# tripoint.net
KiCad netlist of a schematic drawn in EAGLE
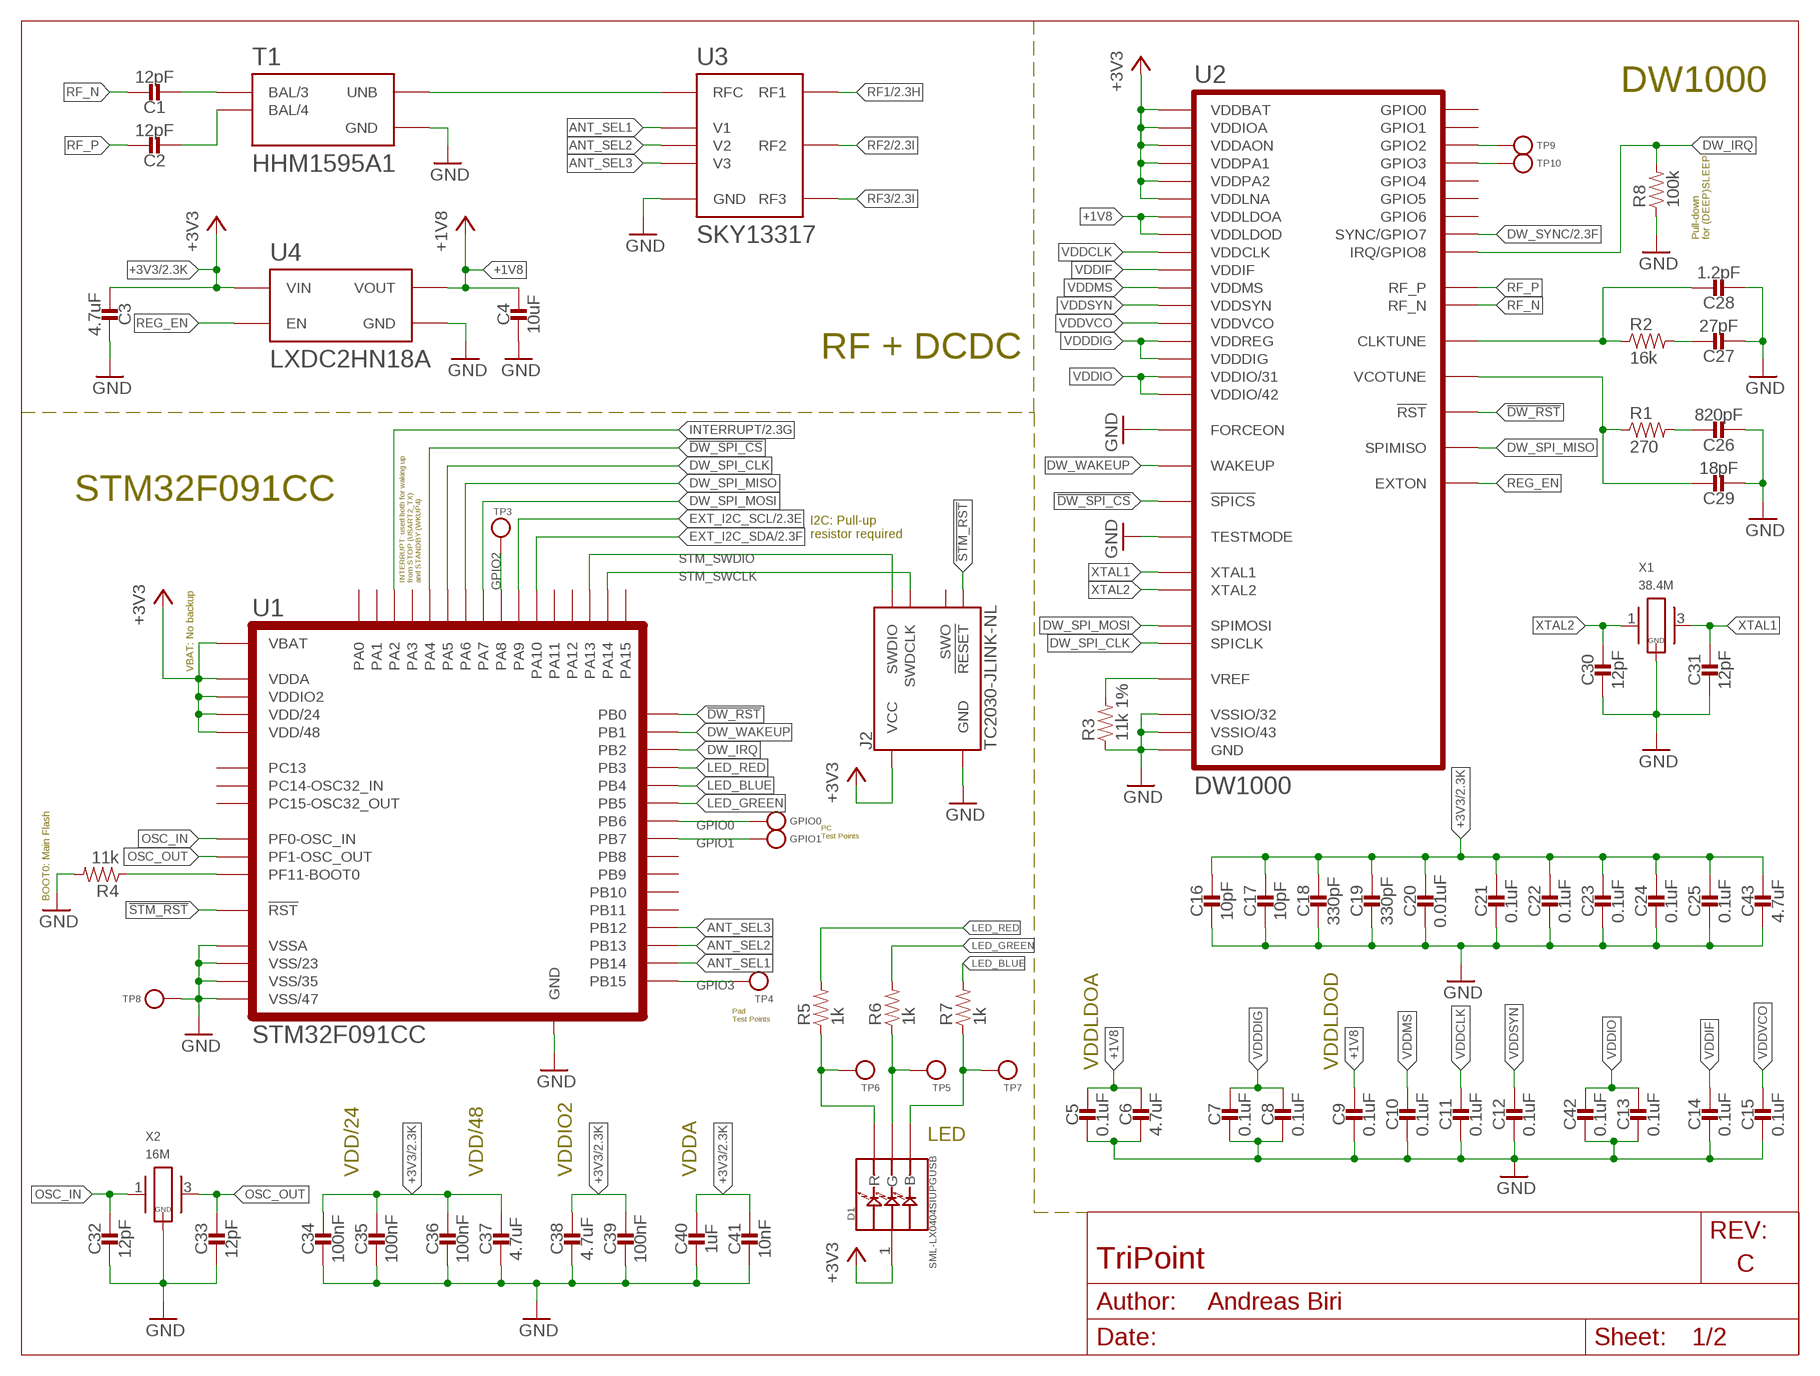
[diagram p0: schematic, sheet 1]
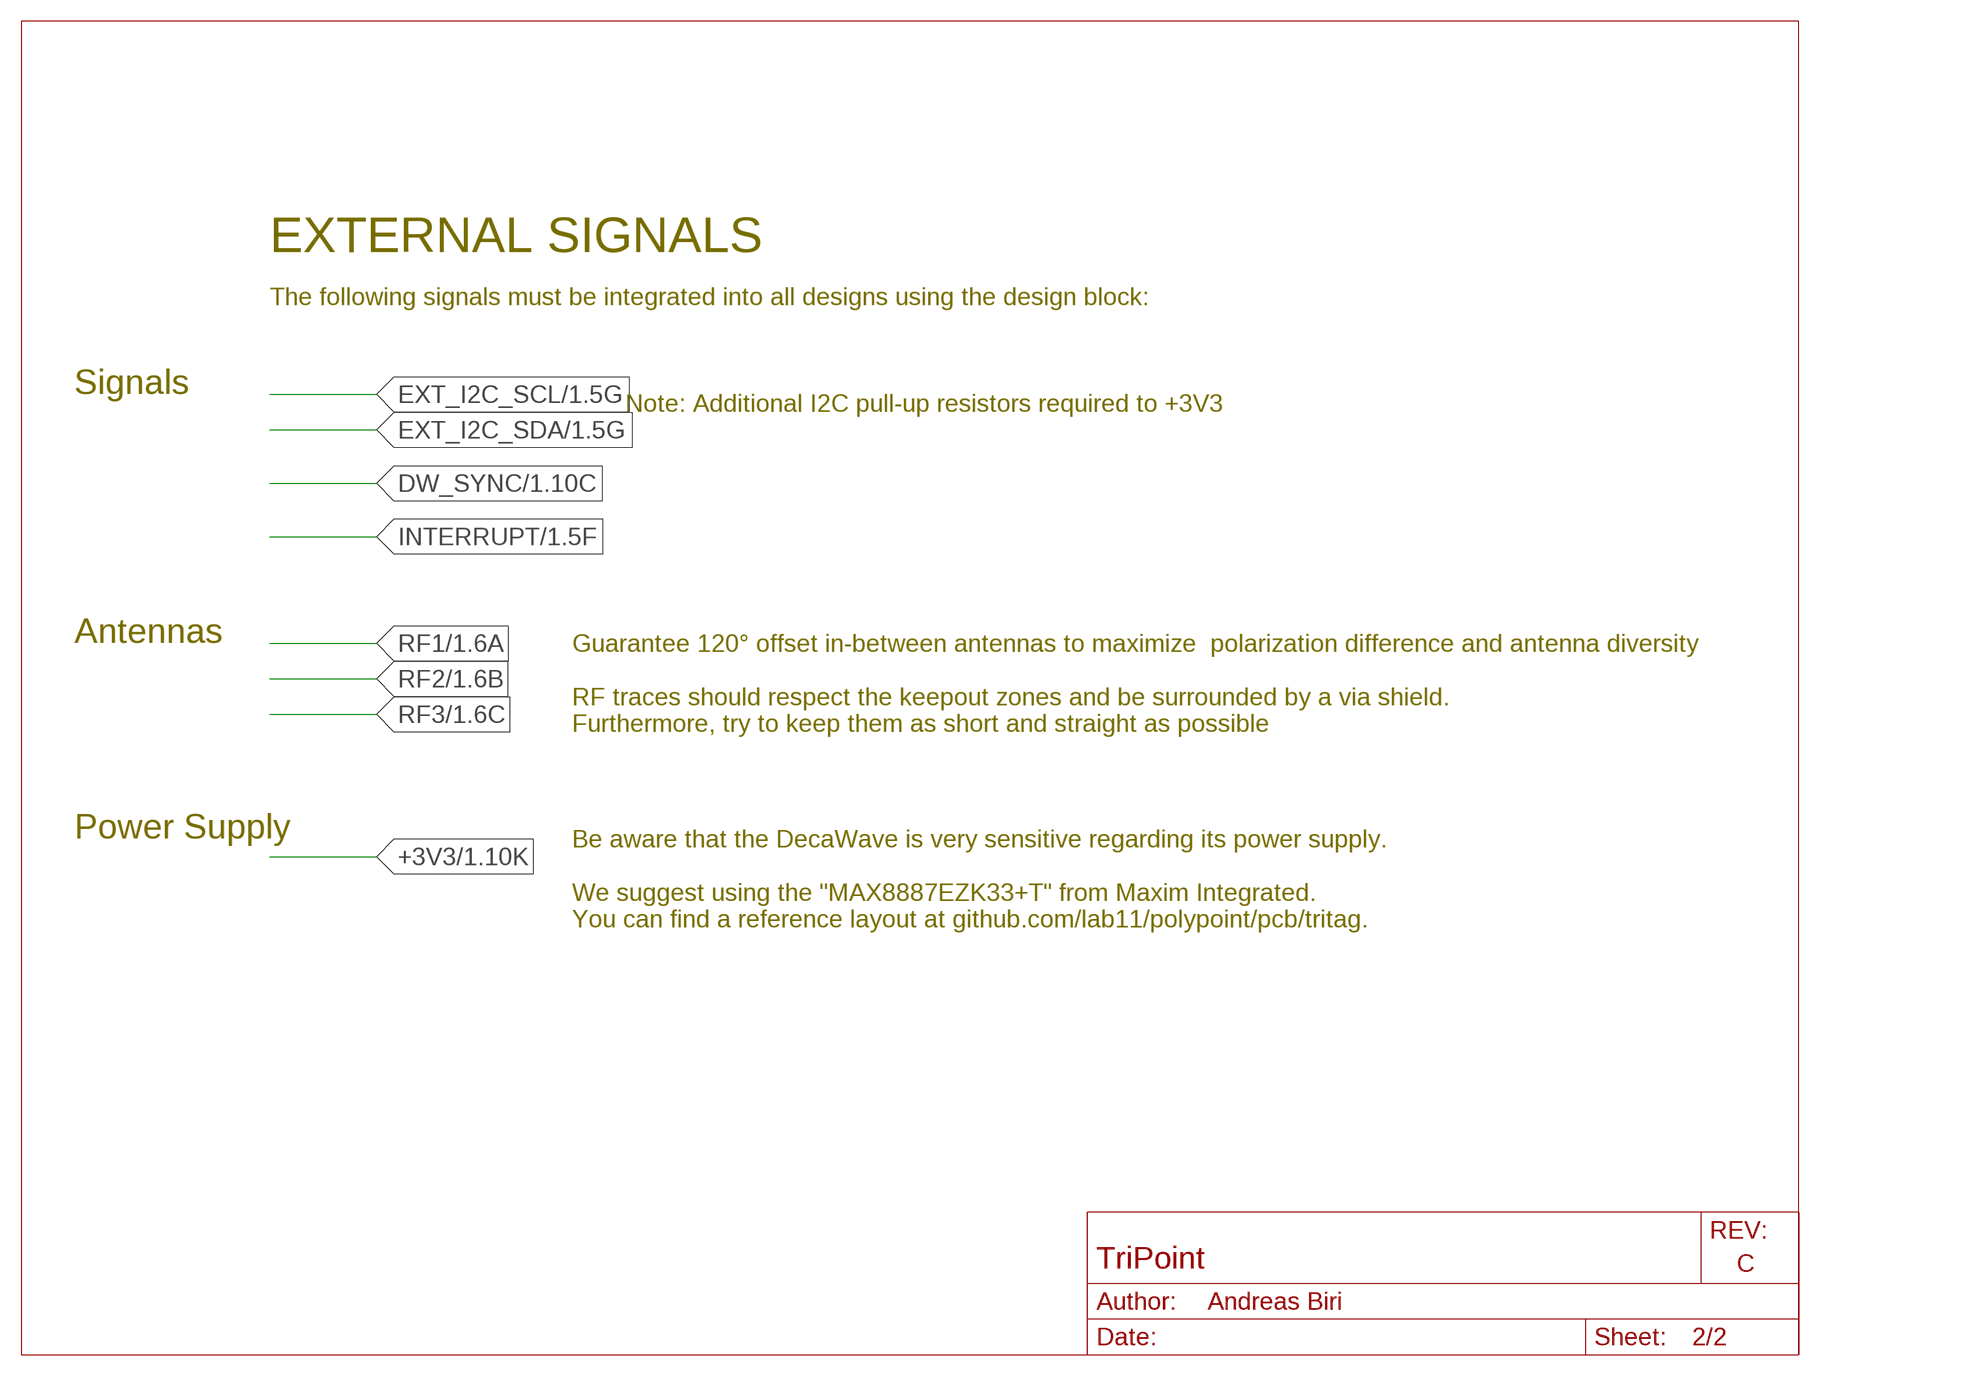
[diagram p1: schematic, sheet 2]

(export (version "E")
  (design (tool "Eeschema 10.0.6"))
  (components
    (comp (ref "C1")
      (value "12pF")
      (footprint "eagle-import:0201_CAP")
      (libsource (lib "eagle-import") (part "CAPACITOR0201_CAP"))
    )
    (comp (ref "C2")
      (value "12pF")
      (footprint "eagle-import:0201_CAP")
      (libsource (lib "eagle-import") (part "CAPACITOR0201_CAP"))
    )
    (comp (ref "C3")
      (value "4.7uF")
      (footprint "eagle-import:0402_CAP")
      (libsource (lib "eagle-import") (part "CAPACITOR0402_CAP"))
    )
    (comp (ref "C4")
      (value "10uF")
      (footprint "eagle-import:0603_CAP")
      (libsource (lib "eagle-import") (part "CAPACITOR0603_CAP"))
    )
    (comp (ref "C5")
      (value "0.1uF")
      (footprint "eagle-import:0402_CAP")
      (libsource (lib "eagle-import") (part "CAPACITOR0402_CAP"))
    )
    (comp (ref "C6")
      (value "4.7uF")
      (footprint "eagle-import:0402_CAP")
      (libsource (lib "eagle-import") (part "CAPACITOR0402_CAP"))
    )
    (comp (ref "C7")
      (value "0.1uF")
      (footprint "eagle-import:0402_CAP")
      (libsource (lib "eagle-import") (part "CAPACITOR0402_CAP"))
    )
    (comp (ref "C8")
      (value "0.1uF")
      (footprint "eagle-import:0402_CAP")
      (libsource (lib "eagle-import") (part "CAPACITOR0402_CAP"))
    )
    (comp (ref "C9")
      (value "0.1uF")
      (footprint "eagle-import:0402_CAP")
      (libsource (lib "eagle-import") (part "CAPACITOR0402_CAP"))
    )
    (comp (ref "C10")
      (value "0.1uF")
      (footprint "eagle-import:0402_CAP")
      (libsource (lib "eagle-import") (part "CAPACITOR0402_CAP"))
    )
    (comp (ref "C11")
      (value "0.1uF")
      (footprint "eagle-import:0402_CAP")
      (libsource (lib "eagle-import") (part "CAPACITOR0402_CAP"))
    )
    (comp (ref "C12")
      (value "0.1uF")
      (footprint "eagle-import:0402_CAP")
      (libsource (lib "eagle-import") (part "CAPACITOR0402_CAP"))
    )
    (comp (ref "C13")
      (value "0.1uF")
      (footprint "eagle-import:0402_CAP")
      (libsource (lib "eagle-import") (part "CAPACITOR0402_CAP"))
    )
    (comp (ref "C14")
      (value "0.1uF")
      (footprint "eagle-import:0402_CAP")
      (libsource (lib "eagle-import") (part "CAPACITOR0402_CAP"))
    )
    (comp (ref "C15")
      (value "0.1uF")
      (footprint "eagle-import:0402_CAP")
      (libsource (lib "eagle-import") (part "CAPACITOR0402_CAP"))
    )
    (comp (ref "C16")
      (value "10pF")
      (footprint "eagle-import:0402_CAP")
      (libsource (lib "eagle-import") (part "CAPACITOR0402_CAP"))
    )
    (comp (ref "C17")
      (value "10pF")
      (footprint "eagle-import:0402_CAP")
      (libsource (lib "eagle-import") (part "CAPACITOR0402_CAP"))
    )
    (comp (ref "C18")
      (value "330pF")
      (footprint "eagle-import:0402_CAP")
      (libsource (lib "eagle-import") (part "CAPACITOR0402_CAP"))
    )
    (comp (ref "C19")
      (value "330pF")
      (footprint "eagle-import:0402_CAP")
      (libsource (lib "eagle-import") (part "CAPACITOR0402_CAP"))
    )
    (comp (ref "C20")
      (value "0.01uF")
      (footprint "eagle-import:0402_CAP")
      (libsource (lib "eagle-import") (part "CAPACITOR0402_CAP"))
    )
    (comp (ref "C21")
      (value "0.1uF")
      (footprint "eagle-import:0402_CAP")
      (libsource (lib "eagle-import") (part "CAPACITOR0402_CAP"))
    )
    (comp (ref "C22")
      (value "0.1uF")
      (footprint "eagle-import:0402_CAP")
      (libsource (lib "eagle-import") (part "CAPACITOR0402_CAP"))
    )
    (comp (ref "C23")
      (value "0.1uF")
      (footprint "eagle-import:0402_CAP")
      (libsource (lib "eagle-import") (part "CAPACITOR0402_CAP"))
    )
    (comp (ref "C24")
      (value "0.1uF")
      (footprint "eagle-import:0402_CAP")
      (libsource (lib "eagle-import") (part "CAPACITOR0402_CAP"))
    )
    (comp (ref "C25")
      (value "0.1uF")
      (footprint "eagle-import:0402_CAP")
      (libsource (lib "eagle-import") (part "CAPACITOR0402_CAP"))
    )
    (comp (ref "C26")
      (value "820pF")
      (footprint "eagle-import:0402_CAP")
      (libsource (lib "eagle-import") (part "CAPACITOR0402_CAP"))
    )
    (comp (ref "C27")
      (value "27pF")
      (footprint "eagle-import:0402_CAP")
      (libsource (lib "eagle-import") (part "CAPACITOR0402_CAP"))
    )
    (comp (ref "C28")
      (value "1.2pF")
      (footprint "eagle-import:0402_CAP")
      (libsource (lib "eagle-import") (part "CAPACITOR0402_CAP"))
    )
    (comp (ref "C29")
      (value "18pF")
      (footprint "eagle-import:0402_CAP")
      (libsource (lib "eagle-import") (part "CAPACITOR0402_CAP"))
    )
    (comp (ref "C30")
      (value "12pF")
      (footprint "eagle-import:0402_CAP")
      (libsource (lib "eagle-import") (part "CAPACITOR0402_CAP"))
    )
    (comp (ref "C31")
      (value "12pF")
      (footprint "eagle-import:0402_CAP")
      (libsource (lib "eagle-import") (part "CAPACITOR0402_CAP"))
    )
    (comp (ref "C32")
      (value "12pF")
      (footprint "eagle-import:0402_CAP")
      (libsource (lib "eagle-import") (part "CAPACITOR0402_CAP"))
    )
    (comp (ref "C33")
      (value "12pF")
      (footprint "eagle-import:0402_CAP")
      (libsource (lib "eagle-import") (part "CAPACITOR0402_CAP"))
    )
    (comp (ref "C34")
      (value "100nF")
      (footprint "eagle-import:0402_CAP")
      (libsource (lib "eagle-import") (part "CAPACITOR0402_CAP"))
    )
    (comp (ref "C35")
      (value "100nF")
      (footprint "eagle-import:0402_CAP")
      (libsource (lib "eagle-import") (part "CAPACITOR0402_CAP"))
    )
    (comp (ref "C36")
      (value "100nF")
      (footprint "eagle-import:0402_CAP")
      (libsource (lib "eagle-import") (part "CAPACITOR0402_CAP"))
    )
    (comp (ref "C37")
      (value "4.7uF")
      (footprint "eagle-import:0402_CAP")
      (libsource (lib "eagle-import") (part "CAPACITOR0402_CAP"))
    )
    (comp (ref "C38")
      (value "4.7uF")
      (footprint "eagle-import:0402_CAP")
      (libsource (lib "eagle-import") (part "CAPACITOR0402_CAP"))
    )
    (comp (ref "C39")
      (value "100nF")
      (footprint "eagle-import:0402_CAP")
      (libsource (lib "eagle-import") (part "CAPACITOR0402_CAP"))
    )
    (comp (ref "C40")
      (value "1uF")
      (footprint "eagle-import:0402_CAP")
      (libsource (lib "eagle-import") (part "CAPACITOR0402_CAP"))
    )
    (comp (ref "C41")
      (value "10nF")
      (footprint "eagle-import:0402_CAP")
      (libsource (lib "eagle-import") (part "CAPACITOR0402_CAP"))
    )
    (comp (ref "C42")
      (value "0.1uF")
      (footprint "eagle-import:0402_CAP")
      (libsource (lib "eagle-import") (part "CAPACITOR0402_CAP"))
    )
    (comp (ref "C43")
      (value "4.7uF")
      (footprint "eagle-import:0402_CAP")
      (libsource (lib "eagle-import") (part "CAPACITOR0402_CAP"))
    )
    (comp (ref "D1")
      (value "SML-LX0404SIUPGUSB")
      (footprint "eagle-import:1MM_SQ_4PAD")
      (fields (field (name "MANUFACTURER") "Lumex Opto"))
      (libsource (lib "eagle-import") (part "SML-LX0404SIUPGUSB"))
    )
    (comp (ref "GPIO0")
      (value "TEST_POINT_0.040IN")
      (footprint "eagle-import:TESTPOINT_0.040IN")
      (libsource (lib "eagle-import") (part "TEST_POINT_0.040IN"))
    )
    (comp (ref "GPIO1")
      (value "TEST_POINT_0.040IN")
      (footprint "eagle-import:TESTPOINT_0.040IN")
      (libsource (lib "eagle-import") (part "TEST_POINT_0.040IN"))
    )
    (comp (ref "J2")
      (value "TC2030-JLINK-NL")
      (footprint "eagle-import:TC2030-IDC-NL")
      (libsource (lib "eagle-import") (part "TC2030-JLINK-NL"))
    )
    (comp (ref "R1")
      (value "270")
      (footprint "eagle-import:0402_RES")
      (libsource (lib "eagle-import") (part "RESISTOR0402_RES"))
    )
    (comp (ref "R2")
      (value "16k")
      (footprint "eagle-import:0402_RES")
      (libsource (lib "eagle-import") (part "RESISTOR0402_RES"))
    )
    (comp (ref "R3")
      (value "11k 1%")
      (footprint "eagle-import:0402_RES")
      (libsource (lib "eagle-import") (part "RESISTOR0402_RES"))
    )
    (comp (ref "R4")
      (value "11k")
      (footprint "eagle-import:0402_RES")
      (libsource (lib "eagle-import") (part "RESISTOR0402_RES"))
    )
    (comp (ref "R5")
      (value "1k")
      (footprint "eagle-import:0402_RES")
      (libsource (lib "eagle-import") (part "RESISTOR0402_RES"))
    )
    (comp (ref "R6")
      (value "1k")
      (footprint "eagle-import:0402_RES")
      (libsource (lib "eagle-import") (part "RESISTOR0402_RES"))
    )
    (comp (ref "R7")
      (value "1k")
      (footprint "eagle-import:0402_RES")
      (libsource (lib "eagle-import") (part "RESISTOR0402_RES"))
    )
    (comp (ref "R8")
      (value "100k")
      (footprint "eagle-import:0402_RES")
      (libsource (lib "eagle-import") (part "RESISTOR0402_RES"))
    )
    (comp (ref "T1")
      (value "HHM1595A1")
      (footprint "eagle-import:EIA-0805")
      (fields (field (name "MANUFACTURER") "TDK Corporation"))
      (libsource (lib "eagle-import") (part "HHM1595A1"))
    )
    (comp (ref "TP3")
      (value "TEST-POINT")
      (footprint "eagle-import:PAD.03X.03")
      (libsource (lib "eagle-import") (part "TEST-POINT"))
    )
    (comp (ref "TP4")
      (value "TEST-POINT")
      (footprint "eagle-import:PAD.03X.03")
      (libsource (lib "eagle-import") (part "TEST-POINT"))
    )
    (comp (ref "TP5")
      (value "TEST-POINT")
      (footprint "eagle-import:PAD.03X.03")
      (libsource (lib "eagle-import") (part "TEST-POINT"))
    )
    (comp (ref "TP6")
      (value "TEST-POINT")
      (footprint "eagle-import:PAD.03X.03")
      (libsource (lib "eagle-import") (part "TEST-POINT"))
    )
    (comp (ref "TP7")
      (value "TEST-POINT")
      (footprint "eagle-import:PAD.03X.03")
      (libsource (lib "eagle-import") (part "TEST-POINT"))
    )
    (comp (ref "TP8")
      (value "TEST-POINT")
      (footprint "eagle-import:PAD.03X.03")
      (libsource (lib "eagle-import") (part "TEST-POINT"))
    )
    (comp (ref "TP9")
      (value "TEST-POINT")
      (footprint "eagle-import:PAD.03X.03")
      (libsource (lib "eagle-import") (part "TEST-POINT"))
    )
    (comp (ref "TP10")
      (value "TEST-POINT")
      (footprint "eagle-import:PAD.03X.03")
      (libsource (lib "eagle-import") (part "TEST-POINT"))
    )
    (comp (ref "U1")
      (value "STM32F091CC")
      (footprint "eagle-import:UFQFPN-48")
      (fields (field (name "MANUFACTURER") "STMicroelectronics") (field (name "MPN") "STM32F091CCU6"))
      (libsource (lib "eagle-import") (part "STM32F091CC"))
    )
    (comp (ref "U2")
      (value "DW1000")
      (footprint "eagle-import:QFN-48-DW1000")
      (fields (field (name "MANUFACTURER") "Decawave Limited") (field (name "MPN") "DW1000-I-TR13"))
      (libsource (lib "eagle-import") (part "DW1000"))
    )
    (comp (ref "U3")
      (value "SKY13317")
      (footprint "eagle-import:MLPQ-UT-8")
      (fields (field (name "MANUFACTURER") "Skyworks Solutions Inc.") (field (name "MPN") "SKY13317-373LF"))
      (libsource (lib "eagle-import") (part "SKY13317"))
    )
    (comp (ref "U4")
      (value "LXDC2HN18A")
      (footprint "eagle-import:LXDC2HN")
      (fields
        (field (name "MANUFACTURER") "Murata Electronics North America")
        (field (name "MPN") "LXDC2HN18A-097")
      )
      (libsource (lib "eagle-import") (part "LXDC2HN18A"))
    )
    (comp (ref "X1")
      (value "38.4M")
      (footprint "eagle-import:FA-20H")
      (description "38.4MHz ±10ppm Crystal 8.5pF 40 Ohms 4-SMD, No Lead")
      (fields (field (name "MANUFACTURER") "EPSON"))
      (libsource (lib "eagle-import") (part "FA-20H"))
    )
    (comp (ref "X2")
      (value "16M")
      (footprint "eagle-import:FA-20H")
      (description "16MHz ±10ppm Crystal 8pF 80 Ohms 4-SMD, No Lead")
      (fields (field (name "MANUFACTURER") "EPSON"))
      (libsource (lib "eagle-import") (part "FA-20H"))
    )
  )
  (nets
    (net (code "1") (name "+1V8") (class "Default")
      (node (ref "C4") (pin "1") (pinfunction "1_1") (pintype "bidirectional"))
      (node (ref "C5") (pin "1") (pinfunction "1_1") (pintype "bidirectional"))
      (node (ref "C6") (pin "1") (pinfunction "1_1") (pintype "bidirectional"))
      (node (ref "C9") (pin "1") (pinfunction "1_1") (pintype "bidirectional"))
      (node (ref "U2") (pin "26") (pinfunction "VDDLDOD_26") (pintype "power_in"))
      (node (ref "U2") (pin "48") (pinfunction "VDDLDOA_48") (pintype "power_in"))
      (node (ref "U4") (pin "3") (pinfunction "VOUT_3") (pintype "power_in"))
    )
    (net (code "2") (name "+3V3") (class "Default")
      (node (ref "C16") (pin "1") (pinfunction "1_1") (pintype "bidirectional"))
      (node (ref "C17") (pin "1") (pinfunction "1_1") (pintype "bidirectional"))
      (node (ref "C18") (pin "1") (pinfunction "1_1") (pintype "bidirectional"))
      (node (ref "C19") (pin "1") (pinfunction "1_1") (pintype "bidirectional"))
      (node (ref "C20") (pin "1") (pinfunction "1_1") (pintype "bidirectional"))
      (node (ref "C21") (pin "1") (pinfunction "1_1") (pintype "bidirectional"))
      (node (ref "C22") (pin "1") (pinfunction "1_1") (pintype "bidirectional"))
      (node (ref "C23") (pin "1") (pinfunction "1_1") (pintype "bidirectional"))
      (node (ref "C24") (pin "1") (pinfunction "1_1") (pintype "bidirectional"))
      (node (ref "C25") (pin "1") (pinfunction "1_1") (pintype "bidirectional"))
      (node (ref "C3") (pin "2") (pinfunction "2_2") (pintype "bidirectional"))
      (node (ref "C34") (pin "1") (pinfunction "1_1") (pintype "bidirectional"))
      (node (ref "C35") (pin "1") (pinfunction "1_1") (pintype "bidirectional"))
      (node (ref "C36") (pin "1") (pinfunction "1_1") (pintype "bidirectional"))
      (node (ref "C37") (pin "1") (pinfunction "1_1") (pintype "bidirectional"))
      (node (ref "C38") (pin "1") (pinfunction "1_1") (pintype "bidirectional"))
      (node (ref "C39") (pin "1") (pinfunction "1_1") (pintype "bidirectional"))
      (node (ref "C40") (pin "1") (pinfunction "1_1") (pintype "bidirectional"))
      (node (ref "C41") (pin "1") (pinfunction "1_1") (pintype "bidirectional"))
      (node (ref "C43") (pin "1") (pinfunction "1_1") (pintype "bidirectional"))
      (node (ref "D1") (pin "1") (pinfunction "VDD_1") (pintype "bidirectional"))
      (node (ref "J2") (pin "1") (pinfunction "VCC_1") (pintype "bidirectional"))
      (node (ref "U1") (pin "1") (pinfunction "VBAT_1") (pintype "power_in"))
      (node (ref "U1") (pin "24") (pinfunction "VDD/24_24") (pintype "power_in"))
      (node (ref "U1") (pin "36") (pinfunction "VDDIO2_36") (pintype "power_in"))
      (node (ref "U1") (pin "48") (pinfunction "VDD/48_48") (pintype "power_in"))
      (node (ref "U1") (pin "9") (pinfunction "VDDA_9") (pintype "power_in"))
      (node (ref "U2") (pin "15") (pinfunction "VDDLNA_15") (pintype "power_in"))
      (node (ref "U2") (pin "18") (pinfunction "VDDPA1_18") (pintype "power_in"))
      (node (ref "U2") (pin "19") (pinfunction "VDDPA2_19") (pintype "power_in"))
      (node (ref "U2") (pin "25") (pinfunction "VDDAON_25") (pintype "power_in"))
      (node (ref "U2") (pin "28") (pinfunction "VDDIOA_28") (pintype "power_in"))
      (node (ref "U2") (pin "47") (pinfunction "VDDBAT_47") (pintype "power_in"))
      (node (ref "U4") (pin "1") (pinfunction "VIN_1") (pintype "power_in"))
    )
    (net (code "3") (name "ANT_SEL1") (class "Default")
      (node (ref "U1") (pin "27") (pinfunction "PB14_27") (pintype "bidirectional"))
      (node (ref "U3") (pin "3") (pinfunction "V1_3") (pintype "bidirectional"))
    )
    (net (code "4") (name "ANT_SEL2") (class "Default")
      (node (ref "U1") (pin "26") (pinfunction "PB13_26") (pintype "bidirectional"))
      (node (ref "U3") (pin "6") (pinfunction "V2_6") (pintype "bidirectional"))
    )
    (net (code "5") (name "ANT_SEL3") (class "Default")
      (node (ref "U1") (pin "25") (pinfunction "PB12_25") (pintype "bidirectional"))
      (node (ref "U3") (pin "7") (pinfunction "V3_7") (pintype "bidirectional"))
    )
    (net (code "6") (name "DW_IRQ") (class "Default")
      (node (ref "R8") (pin "2") (pinfunction "2_2") (pintype "passive"))
      (node (ref "U1") (pin "20") (pinfunction "PB2_20") (pintype "bidirectional"))
      (node (ref "U2") (pin "45") (pinfunction "IRQ/GPIO8_45") (pintype "bidirectional"))
    )
    (net (code "7") (name "DW_SPI_CLK") (class "Default")
      (node (ref "U1") (pin "15") (pinfunction "PA5_15") (pintype "bidirectional"))
      (node (ref "U2") (pin "41") (pinfunction "SPICLK_41") (pintype "input"))
    )
    (net (code "8") (name "DW_SPI_MISO") (class "Default")
      (node (ref "U1") (pin "16") (pinfunction "PA6_16") (pintype "bidirectional"))
      (node (ref "U2") (pin "40") (pinfunction "SPIMISO_40") (pintype "output"))
    )
    (net (code "9") (name "DW_SPI_MOSI") (class "Default")
      (node (ref "U1") (pin "17") (pinfunction "PA7_17") (pintype "bidirectional"))
      (node (ref "U2") (pin "39") (pinfunction "SPIMOSI_39") (pintype "input"))
    )
    (net (code "10") (name "DW_SYNC") (class "Default")
      (node (ref "U2") (pin "29") (pinfunction "SYNC/GPIO7_29") (pintype "bidirectional"))
    )
    (net (code "11") (name "DW_WAKEUP") (class "Default")
      (node (ref "U1") (pin "19") (pinfunction "PB1_19") (pintype "bidirectional"))
      (node (ref "U2") (pin "23") (pinfunction "WAKEUP_23") (pintype "input"))
    )
    (net (code "12") (name "EXT_I2C_SCL") (class "Default")
      (node (ref "U1") (pin "30") (pinfunction "PA9_30") (pintype "bidirectional"))
    )
    (net (code "13") (name "EXT_I2C_SDA") (class "Default")
      (node (ref "U1") (pin "31") (pinfunction "PA10_31") (pintype "bidirectional"))
    )
    (net (code "14") (name "GND") (class "Default")
      (node (ref "C10") (pin "2") (pinfunction "2_2") (pintype "bidirectional"))
      (node (ref "C11") (pin "2") (pinfunction "2_2") (pintype "bidirectional"))
      (node (ref "C12") (pin "2") (pinfunction "2_2") (pintype "bidirectional"))
      (node (ref "C13") (pin "2") (pinfunction "2_2") (pintype "bidirectional"))
      (node (ref "C14") (pin "2") (pinfunction "2_2") (pintype "bidirectional"))
      (node (ref "C15") (pin "2") (pinfunction "2_2") (pintype "bidirectional"))
      (node (ref "C16") (pin "2") (pinfunction "2_2") (pintype "bidirectional"))
      (node (ref "C17") (pin "2") (pinfunction "2_2") (pintype "bidirectional"))
      (node (ref "C18") (pin "2") (pinfunction "2_2") (pintype "bidirectional"))
      (node (ref "C19") (pin "2") (pinfunction "2_2") (pintype "bidirectional"))
      (node (ref "C20") (pin "2") (pinfunction "2_2") (pintype "bidirectional"))
      (node (ref "C21") (pin "2") (pinfunction "2_2") (pintype "bidirectional"))
      (node (ref "C22") (pin "2") (pinfunction "2_2") (pintype "bidirectional"))
      (node (ref "C23") (pin "2") (pinfunction "2_2") (pintype "bidirectional"))
      (node (ref "C24") (pin "2") (pinfunction "2_2") (pintype "bidirectional"))
      (node (ref "C25") (pin "2") (pinfunction "2_2") (pintype "bidirectional"))
      (node (ref "C26") (pin "2") (pinfunction "2_2") (pintype "bidirectional"))
      (node (ref "C27") (pin "2") (pinfunction "2_2") (pintype "bidirectional"))
      (node (ref "C28") (pin "2") (pinfunction "2_2") (pintype "bidirectional"))
      (node (ref "C29") (pin "2") (pinfunction "2_2") (pintype "bidirectional"))
      (node (ref "C3") (pin "1") (pinfunction "1_1") (pintype "bidirectional"))
      (node (ref "C30") (pin "2") (pinfunction "2_2") (pintype "bidirectional"))
      (node (ref "C31") (pin "2") (pinfunction "2_2") (pintype "bidirectional"))
      (node (ref "C32") (pin "2") (pinfunction "2_2") (pintype "bidirectional"))
      (node (ref "C33") (pin "2") (pinfunction "2_2") (pintype "bidirectional"))
      (node (ref "C34") (pin "2") (pinfunction "2_2") (pintype "bidirectional"))
      (node (ref "C35") (pin "2") (pinfunction "2_2") (pintype "bidirectional"))
      (node (ref "C36") (pin "2") (pinfunction "2_2") (pintype "bidirectional"))
      (node (ref "C37") (pin "2") (pinfunction "2_2") (pintype "bidirectional"))
      (node (ref "C38") (pin "2") (pinfunction "2_2") (pintype "bidirectional"))
      (node (ref "C39") (pin "2") (pinfunction "2_2") (pintype "bidirectional"))
      (node (ref "C4") (pin "2") (pinfunction "2_2") (pintype "bidirectional"))
      (node (ref "C40") (pin "2") (pinfunction "2_2") (pintype "bidirectional"))
      (node (ref "C41") (pin "2") (pinfunction "2_2") (pintype "bidirectional"))
      (node (ref "C42") (pin "2") (pinfunction "2_2") (pintype "bidirectional"))
      (node (ref "C43") (pin "2") (pinfunction "2_2") (pintype "bidirectional"))
      (node (ref "C5") (pin "2") (pinfunction "2_2") (pintype "bidirectional"))
      (node (ref "C6") (pin "2") (pinfunction "2_2") (pintype "bidirectional"))
      (node (ref "C7") (pin "2") (pinfunction "2_2") (pintype "bidirectional"))
      (node (ref "C8") (pin "2") (pinfunction "2_2") (pintype "bidirectional"))
      (node (ref "C9") (pin "2") (pinfunction "2_2") (pintype "bidirectional"))
      (node (ref "J2") (pin "5") (pinfunction "GND_5") (pintype "bidirectional"))
      (node (ref "R3") (pin "1") (pinfunction "1_1") (pintype "passive"))
      (node (ref "R4") (pin "2") (pinfunction "2_2") (pintype "passive"))
      (node (ref "R8") (pin "1") (pinfunction "1_1") (pintype "passive"))
      (node (ref "T1") (pin "2") (pinfunction "GND_2") (pintype "power_in"))
      (node (ref "T1") (pin "5") (pinfunction "GND_5") (pintype "power_in"))
      (node (ref "TP8") (pin "P$1") (pinfunction "TESTPOINT_P$1") (pintype "bidirectional"))
      (node (ref "U1") (pin "23") (pinfunction "VSS/23_23") (pintype "power_in"))
      (node (ref "U1") (pin "35") (pinfunction "VSS/35_35") (pintype "power_in"))
      (node (ref "U1") (pin "47") (pinfunction "VSS/47_47") (pintype "power_in"))
      (node (ref "U1") (pin "8") (pinfunction "VSSA_8") (pintype "power_in"))
      (node (ref "U1") (pin "GND") (pinfunction "GND_GND") (pintype "power_in"))
      (node (ref "U2") (pin "22") (pinfunction "FORCEON_22") (pintype "input"))
      (node (ref "U2") (pin "32") (pinfunction "VSSIO/32_32") (pintype "bidirectional"))
      (node (ref "U2") (pin "43") (pinfunction "VSSIO/43_43") (pintype "bidirectional"))
      (node (ref "U2") (pin "46") (pinfunction "TESTMODE_46") (pintype "input"))
      (node (ref "U2") (pin "GND") (pinfunction "GND_GND") (pintype "power_in"))
      (node (ref "U3") (pin "GND") (pinfunction "GND_GND") (pintype "power_in"))
      (node (ref "U4") (pin "4") (pinfunction "GND_4") (pintype "power_in"))
      (node (ref "X1") (pin "2") (pinfunction "GND_2") (pintype "bidirectional"))
      (node (ref "X1") (pin "4") (pinfunction "GND_4") (pintype "bidirectional"))
      (node (ref "X2") (pin "2") (pinfunction "GND_2") (pintype "bidirectional"))
      (node (ref "X2") (pin "4") (pinfunction "GND_4") (pintype "bidirectional"))
    )
    (net (code "15") (name "GPIO0") (class "Default")
      (node (ref "GPIO0") (pin "TESTPOINT") (pinfunction "TESTPOINT_TESTPOINT") (pintype "bidirectional"))
      (node (ref "U1") (pin "42") (pinfunction "PB6_42") (pintype "bidirectional"))
    )
    (net (code "16") (name "GPIO1") (class "Default")
      (node (ref "GPIO1") (pin "TESTPOINT") (pinfunction "TESTPOINT_TESTPOINT") (pintype "bidirectional"))
      (node (ref "U1") (pin "43") (pinfunction "PB7_43") (pintype "bidirectional"))
    )
    (net (code "17") (name "GPIO2") (class "Default")
      (node (ref "TP3") (pin "P$1") (pinfunction "TESTPOINT_P$1") (pintype "bidirectional"))
      (node (ref "U1") (pin "29") (pinfunction "PA8_29") (pintype "bidirectional"))
    )
    (net (code "18") (name "GPIO3") (class "Default")
      (node (ref "TP4") (pin "P$1") (pinfunction "TESTPOINT_P$1") (pintype "bidirectional"))
      (node (ref "U1") (pin "28") (pinfunction "PB15_28") (pintype "bidirectional"))
    )
    (net (code "19") (name "INTERRUPT") (class "Default")
      (node (ref "U1") (pin "12") (pinfunction "PA2_12") (pintype "bidirectional"))
    )
    (net (code "20") (name "LED_BLUE") (class "Default")
      (node (ref "R7") (pin "2") (pinfunction "2_2") (pintype "passive"))
      (node (ref "U1") (pin "40") (pinfunction "PB4_40") (pintype "bidirectional"))
    )
    (net (code "21") (name "LED_GREEN") (class "Default")
      (node (ref "R6") (pin "2") (pinfunction "2_2") (pintype "passive"))
      (node (ref "U1") (pin "41") (pinfunction "PB5_41") (pintype "bidirectional"))
    )
    (net (code "22") (name "LED_RED") (class "Default")
      (node (ref "R5") (pin "2") (pinfunction "2_2") (pintype "passive"))
      (node (ref "U1") (pin "39") (pinfunction "PB3_39") (pintype "bidirectional"))
    )
    (net (code "23") (name "Net-(C1-2)") (class "Default")
      (node (ref "C1") (pin "P$2") (pinfunction "2_P$2") (pintype "bidirectional"))
      (node (ref "T1") (pin "3") (pinfunction "BAL/3_3") (pintype "bidirectional"))
    )
    (net (code "24") (name "Net-(C2-2)") (class "Default")
      (node (ref "C2") (pin "P$2") (pinfunction "2_P$2") (pintype "bidirectional"))
      (node (ref "T1") (pin "4") (pinfunction "BAL/4_4") (pintype "bidirectional"))
    )
    (net (code "25") (name "Net-(C26-Pad1)") (class "Default")
      (node (ref "C26") (pin "1") (pinfunction "1_1") (pintype "bidirectional"))
      (node (ref "R1") (pin "2") (pinfunction "2_2") (pintype "passive"))
    )
    (net (code "26") (name "Net-(C27-Pad1)") (class "Default")
      (node (ref "C27") (pin "1") (pinfunction "1_1") (pintype "bidirectional"))
      (node (ref "R2") (pin "2") (pinfunction "2_2") (pintype "passive"))
    )
    (net (code "27") (name "Net-(D1-B)") (class "Default")
      (node (ref "D1") (pin "3") (pinfunction "B_3") (pintype "output"))
      (node (ref "R7") (pin "1") (pinfunction "1_1") (pintype "passive"))
      (node (ref "TP7") (pin "P$1") (pinfunction "TESTPOINT_P$1") (pintype "bidirectional"))
    )
    (net (code "28") (name "Net-(D1-G)") (class "Default")
      (node (ref "D1") (pin "4") (pinfunction "G_4") (pintype "output"))
      (node (ref "R6") (pin "1") (pinfunction "1_1") (pintype "passive"))
      (node (ref "TP5") (pin "P$1") (pinfunction "TESTPOINT_P$1") (pintype "bidirectional"))
    )
    (net (code "29") (name "Net-(D1-R)") (class "Default")
      (node (ref "D1") (pin "2") (pinfunction "R_2") (pintype "output"))
      (node (ref "R5") (pin "1") (pinfunction "1_1") (pintype "passive"))
      (node (ref "TP6") (pin "P$1") (pinfunction "TESTPOINT_P$1") (pintype "bidirectional"))
    )
    (net (code "30") (name "Net-(T1-UNB)") (class "Default")
      (node (ref "T1") (pin "1") (pinfunction "UNB_1") (pintype "bidirectional"))
      (node (ref "U3") (pin "1") (pinfunction "RFC_1") (pintype "bidirectional"))
    )
    (net (code "31") (name "Net-(TP9-TESTPOINT)") (class "Default")
      (node (ref "TP9") (pin "P$1") (pinfunction "TESTPOINT_P$1") (pintype "bidirectional"))
      (node (ref "U2") (pin "36") (pinfunction "GPIO2_36") (pintype "bidirectional"))
    )
    (net (code "32") (name "Net-(TP10-TESTPOINT)") (class "Default")
      (node (ref "TP10") (pin "P$1") (pinfunction "TESTPOINT_P$1") (pintype "bidirectional"))
      (node (ref "U2") (pin "35") (pinfunction "GPIO3_35") (pintype "bidirectional"))
    )
    (net (code "33") (name "Net-(U1-PF11-BOOT0)") (class "Default")
      (node (ref "R4") (pin "1") (pinfunction "1_1") (pintype "passive"))
      (node (ref "U1") (pin "44") (pinfunction "PF11-BOOT0_44") (pintype "bidirectional"))
    )
    (net (code "34") (name "Net-(U2-CLKTUNE)") (class "Default")
      (node (ref "C28") (pin "1") (pinfunction "1_1") (pintype "bidirectional"))
      (node (ref "R2") (pin "1") (pinfunction "1_1") (pintype "passive"))
      (node (ref "U2") (pin "8") (pinfunction "CLKTUNE_8") (pintype "bidirectional"))
    )
    (net (code "35") (name "Net-(U2-VCOTUNE)") (class "Default")
      (node (ref "C29") (pin "1") (pinfunction "1_1") (pintype "bidirectional"))
      (node (ref "R1") (pin "1") (pinfunction "1_1") (pintype "passive"))
      (node (ref "U2") (pin "12") (pinfunction "VCOTUNE_12") (pintype "bidirectional"))
    )
    (net (code "36") (name "Net-(U2-VREF)") (class "Default")
      (node (ref "R3") (pin "2") (pinfunction "2_2") (pintype "passive"))
      (node (ref "U2") (pin "5") (pinfunction "VREF_5") (pintype "bidirectional"))
    )
    (net (code "37") (name "OSC_IN") (class "Default")
      (node (ref "C32") (pin "1") (pinfunction "1_1") (pintype "bidirectional"))
      (node (ref "U1") (pin "5") (pinfunction "PF0-OSC_IN_5") (pintype "bidirectional"))
      (node (ref "X2") (pin "1") (pinfunction "1_1") (pintype "bidirectional"))
    )
    (net (code "38") (name "OSC_OUT") (class "Default")
      (node (ref "C33") (pin "1") (pinfunction "1_1") (pintype "bidirectional"))
      (node (ref "U1") (pin "6") (pinfunction "PF1-OSC_OUT_6") (pintype "bidirectional"))
      (node (ref "X2") (pin "3") (pinfunction "2_3") (pintype "bidirectional"))
    )
    (net (code "39") (name "REG_EN") (class "Default")
      (node (ref "U2") (pin "21") (pinfunction "EXTON_21") (pintype "output"))
      (node (ref "U4") (pin "2") (pinfunction "EN_2") (pintype "bidirectional"))
    )
    (net (code "40") (name "RF1") (class "Default")
      (node (ref "U3") (pin "4") (pinfunction "RF1_4") (pintype "bidirectional"))
    )
    (net (code "41") (name "RF2") (class "Default")
      (node (ref "U3") (pin "5") (pinfunction "RF2_5") (pintype "bidirectional"))
    )
    (net (code "42") (name "RF3") (class "Default")
      (node (ref "U3") (pin "8") (pinfunction "RF3_8") (pintype "bidirectional"))
    )
    (net (code "43") (name "RF_N") (class "Default")
      (node (ref "C1") (pin "P$1") (pinfunction "1_P$1") (pintype "bidirectional"))
      (node (ref "U2") (pin "17") (pinfunction "RF_N_17") (pintype "bidirectional"))
    )
    (net (code "44") (name "RF_P") (class "Default")
      (node (ref "C2") (pin "P$1") (pinfunction "1_P$1") (pintype "bidirectional"))
      (node (ref "U2") (pin "16") (pinfunction "RF_P_16") (pintype "bidirectional"))
    )
    (net (code "45") (name "STM_SWCLK") (class "Default")
      (node (ref "J2") (pin "4") (pinfunction "SWDCLK_4") (pintype "bidirectional"))
      (node (ref "U1") (pin "37") (pinfunction "PA14_37") (pintype "bidirectional"))
    )
    (net (code "46") (name "STM_SWDIO") (class "Default")
      (node (ref "J2") (pin "2") (pinfunction "SWDIO_2") (pintype "bidirectional"))
      (node (ref "U1") (pin "34") (pinfunction "PA13_34") (pintype "bidirectional"))
    )
    (net (code "47") (name "VDDCLK") (class "Default")
      (node (ref "C11") (pin "1") (pinfunction "1_1") (pintype "bidirectional"))
      (node (ref "U2") (pin "9") (pinfunction "VDDCLK_9") (pintype "power_in"))
    )
    (net (code "48") (name "VDDDIG") (class "Default")
      (node (ref "C7") (pin "1") (pinfunction "1_1") (pintype "bidirectional"))
      (node (ref "C8") (pin "1") (pinfunction "1_1") (pintype "bidirectional"))
      (node (ref "U2") (pin "20") (pinfunction "VDDREG_20") (pintype "power_in"))
      (node (ref "U2") (pin "44") (pinfunction "VDDDIG_44") (pintype "power_in"))
    )
    (net (code "49") (name "VDDIF") (class "Default")
      (node (ref "C14") (pin "1") (pinfunction "1_1") (pintype "bidirectional"))
      (node (ref "U2") (pin "7") (pinfunction "VDDIF_7") (pintype "power_in"))
    )
    (net (code "50") (name "VDDIO") (class "Default")
      (node (ref "C13") (pin "1") (pinfunction "1_1") (pintype "bidirectional"))
      (node (ref "C42") (pin "1") (pinfunction "1_1") (pintype "bidirectional"))
      (node (ref "U2") (pin "31") (pinfunction "VDDIO/31_31") (pintype "power_in"))
      (node (ref "U2") (pin "42") (pinfunction "VDDIO/42_42") (pintype "power_in"))
    )
    (net (code "51") (name "VDDMS") (class "Default")
      (node (ref "C10") (pin "1") (pinfunction "1_1") (pintype "bidirectional"))
      (node (ref "U2") (pin "6") (pinfunction "VDDMS_6") (pintype "power_in"))
    )
    (net (code "52") (name "VDDSYN") (class "Default")
      (node (ref "C12") (pin "1") (pinfunction "1_1") (pintype "bidirectional"))
      (node (ref "U2") (pin "10") (pinfunction "VDDSYN_10") (pintype "power_in"))
    )
    (net (code "53") (name "VDDVCO") (class "Default")
      (node (ref "C15") (pin "1") (pinfunction "1_1") (pintype "bidirectional"))
      (node (ref "U2") (pin "11") (pinfunction "VDDVCO_11") (pintype "power_in"))
    )
    (net (code "54") (name "XTAL1") (class "Default")
      (node (ref "C31") (pin "1") (pinfunction "1_1") (pintype "bidirectional"))
      (node (ref "U2") (pin "3") (pinfunction "XTAL1_3") (pintype "input"))
      (node (ref "X1") (pin "3") (pinfunction "2_3") (pintype "bidirectional"))
    )
    (net (code "55") (name "XTAL2") (class "Default")
      (node (ref "C30") (pin "1") (pinfunction "1_1") (pintype "bidirectional"))
      (node (ref "U2") (pin "4") (pinfunction "XTAL2_4") (pintype "input"))
      (node (ref "X1") (pin "1") (pinfunction "1_1") (pintype "bidirectional"))
    )
    (net (code "56") (name "unconnected-(J2-SWO-Pad6)") (class "Default")
      (node (ref "J2") (pin "6") (pinfunction "SWO_6") (pintype "bidirectional"))
    )
    (net (code "57") (name "unconnected-(U1-PA0-Pad10)") (class "Default")
      (node (ref "U1") (pin "10") (pinfunction "PA0_10") (pintype "bidirectional"))
    )
    (net (code "58") (name "unconnected-(U1-PA1-Pad11)") (class "Default")
      (node (ref "U1") (pin "11") (pinfunction "PA1_11") (pintype "bidirectional"))
    )
    (net (code "59") (name "unconnected-(U1-PA3-Pad13)") (class "Default")
      (node (ref "U1") (pin "13") (pinfunction "PA3_13") (pintype "bidirectional"))
    )
    (net (code "60") (name "unconnected-(U1-PA11-Pad32)") (class "Default")
      (node (ref "U1") (pin "32") (pinfunction "PA11_32") (pintype "bidirectional"))
    )
    (net (code "61") (name "unconnected-(U1-PA12-Pad33)") (class "Default")
      (node (ref "U1") (pin "33") (pinfunction "PA12_33") (pintype "bidirectional"))
    )
    (net (code "62") (name "unconnected-(U1-PA15-Pad38)") (class "Default")
      (node (ref "U1") (pin "38") (pinfunction "PA15_38") (pintype "bidirectional"))
    )
    (net (code "63") (name "unconnected-(U1-PB8-Pad45)") (class "Default")
      (node (ref "U1") (pin "45") (pinfunction "PB8_45") (pintype "bidirectional"))
    )
    (net (code "64") (name "unconnected-(U1-PB9-Pad46)") (class "Default")
      (node (ref "U1") (pin "46") (pinfunction "PB9_46") (pintype "bidirectional"))
    )
    (net (code "65") (name "unconnected-(U1-PB10-Pad21)") (class "Default")
      (node (ref "U1") (pin "21") (pinfunction "PB10_21") (pintype "bidirectional"))
    )
    (net (code "66") (name "unconnected-(U1-PB11-Pad22)") (class "Default")
      (node (ref "U1") (pin "22") (pinfunction "PB11_22") (pintype "bidirectional"))
    )
    (net (code "67") (name "unconnected-(U1-PC13-Pad2)") (class "Default")
      (node (ref "U1") (pin "2") (pinfunction "PC13_2") (pintype "bidirectional"))
    )
    (net (code "68") (name "unconnected-(U1-PC14-OSC32_IN-Pad3)") (class "Default")
      (node (ref "U1") (pin "3") (pinfunction "PC14-OSC32_IN_3") (pintype "bidirectional"))
    )
    (net (code "69") (name "unconnected-(U1-PC15-OSC32_OUT-Pad4)") (class "Default")
      (node (ref "U1") (pin "4") (pinfunction "PC15-OSC32_OUT_4") (pintype "bidirectional"))
    )
    (net (code "70") (name "unconnected-(U2-GPIO0-Pad38)") (class "Default")
      (node (ref "U2") (pin "38") (pinfunction "GPIO0_38") (pintype "bidirectional"))
    )
    (net (code "71") (name "unconnected-(U2-GPIO1-Pad37)") (class "Default")
      (node (ref "U2") (pin "37") (pinfunction "GPIO1_37") (pintype "bidirectional"))
    )
    (net (code "72") (name "unconnected-(U2-GPIO4-Pad34)") (class "Default")
      (node (ref "U2") (pin "34") (pinfunction "GPIO4_34") (pintype "bidirectional"))
    )
    (net (code "73") (name "unconnected-(U2-GPIO5-Pad33)") (class "Default")
      (node (ref "U2") (pin "33") (pinfunction "GPIO5_33") (pintype "bidirectional"))
    )
    (net (code "74") (name "unconnected-(U2-GPIO6-Pad30)") (class "Default")
      (node (ref "U2") (pin "30") (pinfunction "GPIO6_30") (pintype "bidirectional"))
    )
    (net (code "75") (name "~{DW_RST}") (class "Default")
      (node (ref "U1") (pin "18") (pinfunction "PB0_18") (pintype "bidirectional"))
      (node (ref "U2") (pin "27") (pinfunction "~{RST}_27") (pintype "bidirectional"))
    )
    (net (code "76") (name "~{DW_SPI_CS}") (class "Default")
      (node (ref "U1") (pin "14") (pinfunction "PA4_14") (pintype "bidirectional"))
      (node (ref "U2") (pin "24") (pinfunction "~{SPICS}_24") (pintype "input"))
    )
    (net (code "77") (name "~{STM_RST}") (class "Default")
      (node (ref "J2") (pin "3") (pinfunction "~{RESET}_3") (pintype "bidirectional"))
      (node (ref "U1") (pin "7") (pinfunction "~{RST}_7") (pintype "bidirectional"))
    )
  )
)
